# Control_Board_v1_1.net
KiCad netlist of a schematic drawn in EAGLE
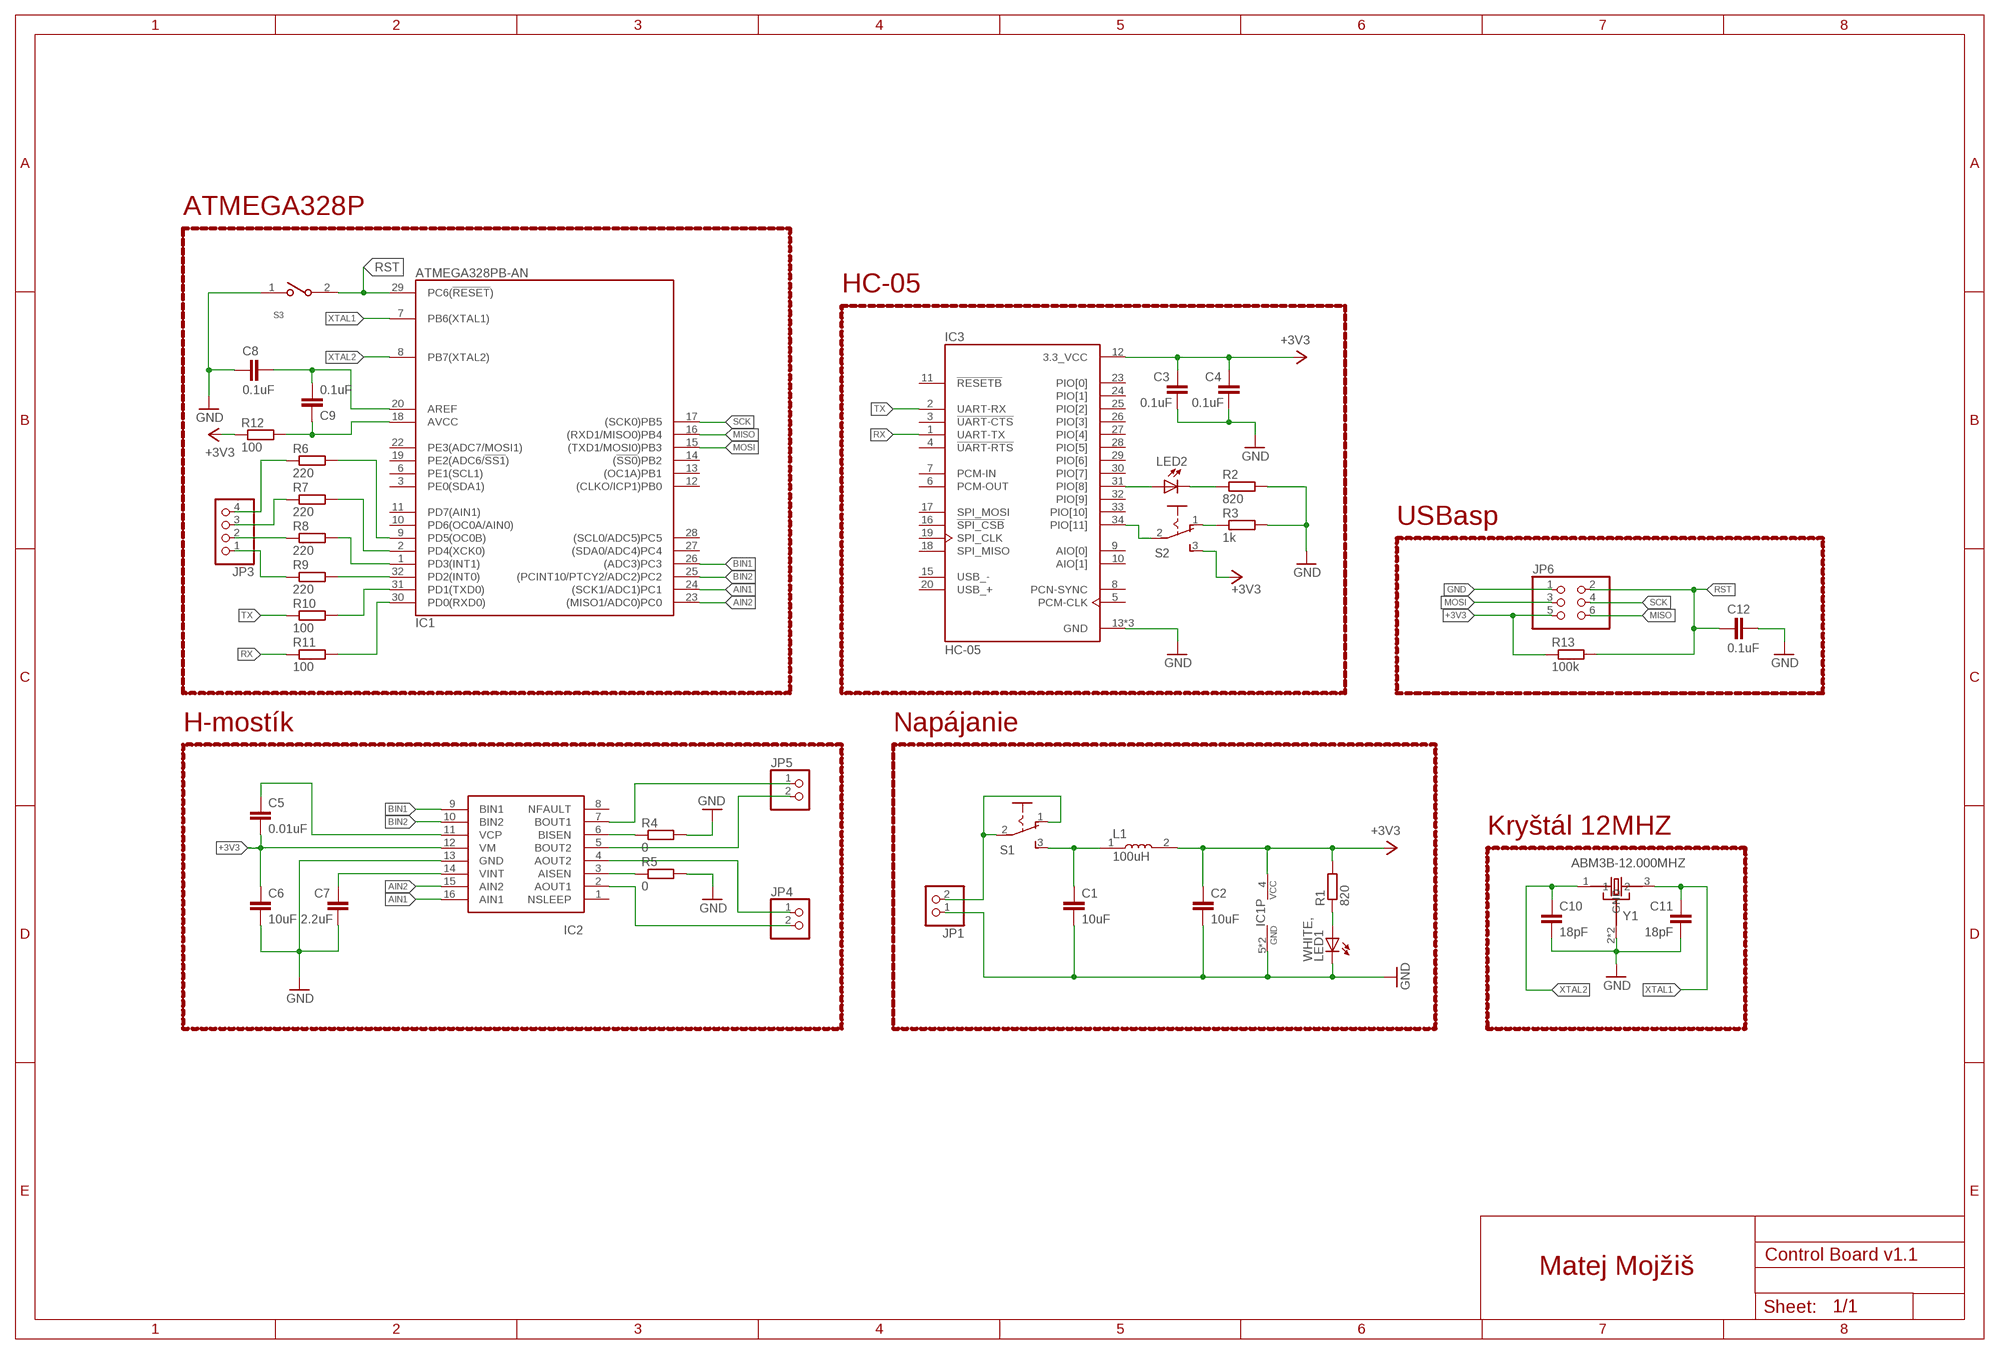
[diagram p0: schematic, sheet 1]

(export (version "E")
  (design (tool "Eeschema 10.0.6"))
  (components
    (comp (ref "C1")
      (value "10uF")
      (footprint "eagle-import:C0805")
      (libsource (lib "eagle-import") (part "C-EUC0805"))
    )
    (comp (ref "C2")
      (value "10uF")
      (footprint "eagle-import:C0805")
      (libsource (lib "eagle-import") (part "C-EUC0805"))
    )
    (comp (ref "C3")
      (value "0.1uF")
      (footprint "eagle-import:C0805")
      (libsource (lib "eagle-import") (part "C-EUC0805"))
    )
    (comp (ref "C4")
      (value "0.1uF")
      (footprint "eagle-import:C0805")
      (libsource (lib "eagle-import") (part "C-EUC0805"))
    )
    (comp (ref "C5")
      (value "0.01uF")
      (footprint "eagle-import:C0805")
      (libsource (lib "eagle-import") (part "C-EUC0805"))
    )
    (comp (ref "C6")
      (value "10uF")
      (footprint "eagle-import:C0805")
      (libsource (lib "eagle-import") (part "C-EUC0805"))
    )
    (comp (ref "C7")
      (value "2.2uF")
      (footprint "eagle-import:C0805")
      (libsource (lib "eagle-import") (part "C-EUC0805"))
    )
    (comp (ref "C8")
      (value "0.1uF")
      (footprint "eagle-import:C0805")
      (libsource (lib "eagle-import") (part "C-EUC0805"))
    )
    (comp (ref "C9")
      (value "0.1uF")
      (footprint "eagle-import:C0805")
      (libsource (lib "eagle-import") (part "C-EUC0805"))
    )
    (comp (ref "C10")
      (value "18pF")
      (footprint "eagle-import:C0805")
      (libsource (lib "eagle-import") (part "C-EUC0805"))
    )
    (comp (ref "C11")
      (value "18pF")
      (footprint "eagle-import:C0805")
      (libsource (lib "eagle-import") (part "C-EUC0805"))
    )
    (comp (ref "C12")
      (value "0.1uF")
      (footprint "eagle-import:C0805")
      (libsource (lib "eagle-import") (part "C-EUC0805"))
    )
    (comp (ref "IC1")
      (value "ATMEGA328PB-AN")
      (footprint "eagle-import:QFP32_7X7_0.80")
      (libsource (lib "eagle-import") (part "ATMEGA328PB-AN"))
    )
    (comp (ref "IC2")
      (value "DVR8833SUPERFICIAL")
      (footprint "eagle-import:PWP16")
      (libsource (lib "eagle-import") (part "DVR8833SUPERFICIAL"))
    )
    (comp (ref "IC3")
      (value "HC-05")
      (footprint "eagle-import:XCVR_HC-05")
      (fields (field (name "MF") "Bel Power solution"))
      (libsource (lib "eagle-import") (part "HC-05"))
    )
    (comp (ref "JP1")
      (value "PINHD-1X2/90")
      (footprint "eagle-import:1X02_90")
      (libsource (lib "eagle-import") (part "PINHD-1X2/90"))
    )
    (comp (ref "JP3")
      (value "PINHD-1X4")
      (footprint "eagle-import:1X04")
      (libsource (lib "eagle-import") (part "PINHD-1X4"))
    )
    (comp (ref "JP4")
      (value "PINHD-1X2/90")
      (footprint "eagle-import:1X02_90")
      (libsource (lib "eagle-import") (part "PINHD-1X2/90"))
    )
    (comp (ref "JP5")
      (value "PINHD-1X2/90")
      (footprint "eagle-import:1X02_90")
      (libsource (lib "eagle-import") (part "PINHD-1X2/90"))
    )
    (comp (ref "JP6")
      (value "PINHD-2X3")
      (footprint "eagle-import:2X03")
      (libsource (lib "eagle-import") (part "PINHD-2X3"))
    )
    (comp (ref "L1")
      (value "100uH")
      (footprint "eagle-import:INDC2012X87N")
      (fields (field (name "MF") "TDK") (field (name "MP") "MLF2012C330KT000"))
      (libsource (lib "eagle-import") (part "MLF2012C330KT000"))
    )
    (comp (ref "LED1")
      (value "WHITE,")
      (footprint "eagle-import:CHIPLED_0805")
      (libsource (lib "eagle-import") (part "LEDCHIPLED_0805"))
    )
    (comp (ref "LED2")
      (value "RED")
      (footprint "eagle-import:CHIPLED_0805")
      (libsource (lib "eagle-import") (part "LEDCHIPLED_0805"))
    )
    (comp (ref "R1")
      (value "820")
      (footprint "eagle-import:R0805")
      (libsource (lib "eagle-import") (part "R-EU_R0805"))
    )
    (comp (ref "R2")
      (value "820")
      (footprint "eagle-import:R0805")
      (libsource (lib "eagle-import") (part "R-EU_R0805"))
    )
    (comp (ref "R3")
      (value "1k")
      (footprint "eagle-import:R0805")
      (libsource (lib "eagle-import") (part "R-EU_R0805"))
    )
    (comp (ref "R4")
      (value "0")
      (footprint "eagle-import:R0805")
      (libsource (lib "eagle-import") (part "R-EU_R0805"))
    )
    (comp (ref "R5")
      (value "0")
      (footprint "eagle-import:R0805")
      (libsource (lib "eagle-import") (part "R-EU_R0805"))
    )
    (comp (ref "R6")
      (value "220")
      (footprint "eagle-import:R0805")
      (libsource (lib "eagle-import") (part "R-EU_R0805"))
    )
    (comp (ref "R7")
      (value "220")
      (footprint "eagle-import:R0805")
      (libsource (lib "eagle-import") (part "R-EU_R0805"))
    )
    (comp (ref "R8")
      (value "220")
      (footprint "eagle-import:R0805")
      (libsource (lib "eagle-import") (part "R-EU_R0805"))
    )
    (comp (ref "R9")
      (value "220")
      (footprint "eagle-import:R0805")
      (libsource (lib "eagle-import") (part "R-EU_R0805"))
    )
    (comp (ref "R10")
      (value "100")
      (footprint "eagle-import:R0805")
      (libsource (lib "eagle-import") (part "R-EU_R0805"))
    )
    (comp (ref "R11")
      (value "100")
      (footprint "eagle-import:R0805")
      (libsource (lib "eagle-import") (part "R-EU_R0805"))
    )
    (comp (ref "R12")
      (value "100")
      (footprint "eagle-import:R0805")
      (libsource (lib "eagle-import") (part "R-EU_R0805"))
    )
    (comp (ref "R13")
      (value "100k")
      (footprint "eagle-import:R0805")
      (libsource (lib "eagle-import") (part "R-EU_R0805"))
    )
    (comp (ref "S1")
      (value "255SB")
      (footprint "eagle-import:255SB")
      (libsource (lib "eagle-import") (part "255SB"))
    )
    (comp (ref "S2")
      (value "255SB")
      (footprint "eagle-import:255SB")
      (libsource (lib "eagle-import") (part "255SB"))
    )
    (comp (ref "S3")
      (value "147873-2")
      (footprint "eagle-import:SW_147873-2")
      (fields (field (name "MF") "TE Connectivity"))
      (libsource (lib "eagle-import") (part "147873-2"))
    )
    (comp (ref "Y1")
      (value "ABM3B-12.000MHZ")
      (footprint "eagle-import:OSCSC500X320X110-4N")
      (fields (field (name "MF") "Abracon") (field (name "MP") "ABM3B-8.000MHZ-B2-T"))
      (libsource (lib "eagle-import") (part "ABM3B-8.000MHZ-B2-T"))
    )
  )
  (nets
    (net (code "1") (name "+3V3") (class "Default")
      (node (ref "C2") (pin "1") (pinfunction "1_1") (pintype "passive"))
      (node (ref "C3") (pin "1") (pinfunction "1_1") (pintype "passive"))
      (node (ref "C4") (pin "1") (pinfunction "1_1") (pintype "passive"))
      (node (ref "C5") (pin "2") (pinfunction "2_2") (pintype "passive"))
      (node (ref "C6") (pin "1") (pinfunction "1_1") (pintype "passive"))
      (node (ref "IC1") (pin "4") (pinfunction "VCC_4") (pintype "power_in"))
      (node (ref "IC2") (pin "12") (pinfunction "VM_12") (pintype "bidirectional"))
      (node (ref "IC3") (pin "12") (pinfunction "3.3_VCC_12") (pintype "power_in"))
      (node (ref "JP6") (pin "5") (pinfunction "5_5") (pintype "passive"))
      (node (ref "L1") (pin "2") (pinfunction "2_2") (pintype "passive"))
      (node (ref "R1") (pin "2") (pinfunction "2_2") (pintype "passive"))
      (node (ref "R12") (pin "1") (pinfunction "1_1") (pintype "passive"))
      (node (ref "R13") (pin "1") (pinfunction "1_1") (pintype "passive"))
      (node (ref "S2") (pin "3") (pinfunction "S_3") (pintype "passive"))
    )
    (net (code "2") (name "AIN1") (class "Default")
      (node (ref "IC1") (pin "24") (pinfunction "(SCK1/ADC1)PC1_24") (pintype "bidirectional"))
      (node (ref "IC2") (pin "16") (pinfunction "AIN1_16") (pintype "bidirectional"))
    )
    (net (code "3") (name "AIN2") (class "Default")
      (node (ref "IC1") (pin "23") (pinfunction "(MISO1/ADC0)PC0_23") (pintype "bidirectional"))
      (node (ref "IC2") (pin "15") (pinfunction "AIN2_15") (pintype "bidirectional"))
    )
    (net (code "4") (name "BIN1") (class "Default")
      (node (ref "IC1") (pin "26") (pinfunction "(ADC3)PC3_26") (pintype "bidirectional"))
      (node (ref "IC2") (pin "9") (pinfunction "BIN1_9") (pintype "bidirectional"))
    )
    (net (code "5") (name "BIN2") (class "Default")
      (node (ref "IC1") (pin "25") (pinfunction "(PCINT10/PTCY2/ADC2)PC2_25") (pintype "bidirectional"))
      (node (ref "IC2") (pin "10") (pinfunction "BIN2_10") (pintype "bidirectional"))
    )
    (net (code "6") (name "GND") (class "Default")
      (node (ref "C1") (pin "2") (pinfunction "2_2") (pintype "passive"))
      (node (ref "C10") (pin "2") (pinfunction "2_2") (pintype "passive"))
      (node (ref "C11") (pin "2") (pinfunction "2_2") (pintype "passive"))
      (node (ref "C12") (pin "1") (pinfunction "1_1") (pintype "passive"))
      (node (ref "C2") (pin "2") (pinfunction "2_2") (pintype "passive"))
      (node (ref "C3") (pin "2") (pinfunction "2_2") (pintype "passive"))
      (node (ref "C4") (pin "2") (pinfunction "2_2") (pintype "passive"))
      (node (ref "C6") (pin "2") (pinfunction "2_2") (pintype "passive"))
      (node (ref "C7") (pin "2") (pinfunction "2_2") (pintype "passive"))
      (node (ref "C8") (pin "2") (pinfunction "2_2") (pintype "passive"))
      (node (ref "IC1") (pin "21") (pinfunction "GND_21") (pintype "power_in"))
      (node (ref "IC1") (pin "5") (pinfunction "GND_5") (pintype "power_in"))
      (node (ref "IC2") (pin "13") (pinfunction "GND_13") (pintype "bidirectional"))
      (node (ref "IC3") (pin "13") (pinfunction "GND_13") (pintype "power_in"))
      (node (ref "IC3") (pin "21") (pinfunction "GND_21") (pintype "power_in"))
      (node (ref "IC3") (pin "22") (pinfunction "GND_22") (pintype "power_in"))
      (node (ref "JP1") (pin "1") (pinfunction "1_1") (pintype "passive"))
      (node (ref "JP6") (pin "1") (pinfunction "1_1") (pintype "passive"))
      (node (ref "LED1") (pin "C") (pinfunction "C_C") (pintype "passive"))
      (node (ref "R2") (pin "2") (pinfunction "2_2") (pintype "passive"))
      (node (ref "R3") (pin "2") (pinfunction "2_2") (pintype "passive"))
      (node (ref "R4") (pin "2") (pinfunction "2_2") (pintype "passive"))
      (node (ref "R5") (pin "2") (pinfunction "2_2") (pintype "passive"))
      (node (ref "S3") (pin "1") (pinfunction "1_1") (pintype "passive"))
      (node (ref "Y1") (pin "2") (pinfunction "GND_2") (pintype "passive"))
      (node (ref "Y1") (pin "4") (pinfunction "GND_4") (pintype "passive"))
    )
    (net (code "7") (name "MISO") (class "Default")
      (node (ref "IC1") (pin "16") (pinfunction "(RXD1/MISO0)PB4_16") (pintype "bidirectional"))
      (node (ref "JP6") (pin "6") (pinfunction "6_6") (pintype "passive"))
    )
    (net (code "8") (name "MOSI") (class "Default")
      (node (ref "IC1") (pin "15") (pinfunction "(TXD1/MOSI0)PB3_15") (pintype "bidirectional"))
      (node (ref "JP6") (pin "3") (pinfunction "3_3") (pintype "passive"))
    )
    (net (code "9") (name "Net-(IC1A-AREF)") (class "Default")
      (node (ref "C8") (pin "1") (pinfunction "1_1") (pintype "passive"))
      (node (ref "C9") (pin "2") (pinfunction "2_2") (pintype "passive"))
      (node (ref "IC1") (pin "20") (pinfunction "AREF_20") (pintype "passive"))
    )
    (net (code "10") (name "Net-(IC1A-AVCC)") (class "Default")
      (node (ref "C9") (pin "1") (pinfunction "1_1") (pintype "passive"))
      (node (ref "IC1") (pin "18") (pinfunction "AVCC_18") (pintype "power_in"))
      (node (ref "R12") (pin "2") (pinfunction "2_2") (pintype "passive"))
    )
    (net (code "11") (name "Net-(IC1A-PD0(RXD0))") (class "Default")
      (node (ref "IC1") (pin "30") (pinfunction "PD0(RXD0)_30") (pintype "bidirectional"))
      (node (ref "R11") (pin "2") (pinfunction "2_2") (pintype "passive"))
    )
    (net (code "12") (name "Net-(IC1A-PD1(TXD0))") (class "Default")
      (node (ref "IC1") (pin "31") (pinfunction "PD1(TXD0)_31") (pintype "bidirectional"))
      (node (ref "R10") (pin "2") (pinfunction "2_2") (pintype "passive"))
    )
    (net (code "13") (name "Net-(IC1A-PD2(INT0))") (class "Default")
      (node (ref "IC1") (pin "32") (pinfunction "PD2(INT0)_32") (pintype "bidirectional"))
      (node (ref "R9") (pin "2") (pinfunction "2_2") (pintype "passive"))
    )
    (net (code "14") (name "Net-(IC1A-PD3(INT1))") (class "Default")
      (node (ref "IC1") (pin "1") (pinfunction "PD3(INT1)_1") (pintype "bidirectional"))
      (node (ref "R8") (pin "2") (pinfunction "2_2") (pintype "passive"))
    )
    (net (code "15") (name "Net-(IC1A-PD4(XCK0))") (class "Default")
      (node (ref "IC1") (pin "2") (pinfunction "PD4(XCK0)_2") (pintype "bidirectional"))
      (node (ref "R7") (pin "2") (pinfunction "2_2") (pintype "passive"))
    )
    (net (code "16") (name "Net-(IC1A-PD5(OC0B))") (class "Default")
      (node (ref "IC1") (pin "9") (pinfunction "PD5(OC0B)_9") (pintype "bidirectional"))
      (node (ref "R6") (pin "2") (pinfunction "2_2") (pintype "passive"))
    )
    (net (code "17") (name "Net-(IC2-AISEN)") (class "Default")
      (node (ref "IC2") (pin "3") (pinfunction "AISEN_3") (pintype "bidirectional"))
      (node (ref "R5") (pin "1") (pinfunction "1_1") (pintype "passive"))
    )
    (net (code "18") (name "Net-(IC2-AOUT1)") (class "Default")
      (node (ref "IC2") (pin "2") (pinfunction "AOUT1_2") (pintype "bidirectional"))
      (node (ref "JP4") (pin "2") (pinfunction "2_2") (pintype "passive"))
    )
    (net (code "19") (name "Net-(IC2-AOUT2)") (class "Default")
      (node (ref "IC2") (pin "4") (pinfunction "AOUT2_4") (pintype "bidirectional"))
      (node (ref "JP4") (pin "1") (pinfunction "1_1") (pintype "passive"))
    )
    (net (code "20") (name "Net-(IC2-BISEN)") (class "Default")
      (node (ref "IC2") (pin "6") (pinfunction "BISEN_6") (pintype "bidirectional"))
      (node (ref "R4") (pin "1") (pinfunction "1_1") (pintype "passive"))
    )
    (net (code "21") (name "Net-(IC2-BOUT1)") (class "Default")
      (node (ref "IC2") (pin "7") (pinfunction "BOUT1_7") (pintype "bidirectional"))
      (node (ref "JP5") (pin "1") (pinfunction "1_1") (pintype "passive"))
    )
    (net (code "22") (name "Net-(IC2-BOUT2)") (class "Default")
      (node (ref "IC2") (pin "5") (pinfunction "BOUT2_5") (pintype "bidirectional"))
      (node (ref "JP5") (pin "2") (pinfunction "2_2") (pintype "passive"))
    )
    (net (code "23") (name "Net-(IC2-VCP)") (class "Default")
      (node (ref "C5") (pin "1") (pinfunction "1_1") (pintype "passive"))
      (node (ref "IC2") (pin "11") (pinfunction "VCP_11") (pintype "bidirectional"))
    )
    (net (code "24") (name "Net-(IC2-VINT)") (class "Default")
      (node (ref "C7") (pin "1") (pinfunction "1_1") (pintype "passive"))
      (node (ref "IC2") (pin "14") (pinfunction "VINT_14") (pintype "bidirectional"))
    )
    (net (code "25") (name "Net-(IC3-PIO[8])") (class "Default")
      (node (ref "IC3") (pin "31") (pinfunction "PIO[8]_31") (pintype "bidirectional"))
      (node (ref "LED2") (pin "A") (pinfunction "A_A") (pintype "passive"))
    )
    (net (code "26") (name "Net-(IC3-PIO[11])") (class "Default")
      (node (ref "IC3") (pin "34") (pinfunction "PIO[11]_34") (pintype "bidirectional"))
      (node (ref "S2") (pin "2") (pinfunction "P_2") (pintype "passive"))
    )
    (net (code "27") (name "Net-(JP3-Pad1)") (class "Default")
      (node (ref "JP3") (pin "1") (pinfunction "1_1") (pintype "passive"))
      (node (ref "R9") (pin "1") (pinfunction "1_1") (pintype "passive"))
    )
    (net (code "28") (name "Net-(JP3-Pad2)") (class "Default")
      (node (ref "JP3") (pin "2") (pinfunction "2_2") (pintype "passive"))
      (node (ref "R8") (pin "1") (pinfunction "1_1") (pintype "passive"))
    )
    (net (code "29") (name "Net-(JP3-Pad3)") (class "Default")
      (node (ref "JP3") (pin "3") (pinfunction "3_3") (pintype "passive"))
      (node (ref "R7") (pin "1") (pinfunction "1_1") (pintype "passive"))
    )
    (net (code "30") (name "Net-(JP3-Pad4)") (class "Default")
      (node (ref "JP3") (pin "4") (pinfunction "4_4") (pintype "passive"))
      (node (ref "R6") (pin "1") (pinfunction "1_1") (pintype "passive"))
    )
    (net (code "31") (name "Net-(LED1-PadA)") (class "Default")
      (node (ref "LED1") (pin "A") (pinfunction "A_A") (pintype "passive"))
      (node (ref "R1") (pin "1") (pinfunction "1_1") (pintype "passive"))
    )
    (net (code "32") (name "Net-(LED2-PadC)") (class "Default")
      (node (ref "LED2") (pin "C") (pinfunction "C_C") (pintype "passive"))
      (node (ref "R2") (pin "1") (pinfunction "1_1") (pintype "passive"))
    )
    (net (code "33") (name "Net-(S1-O)") (class "Default")
      (node (ref "JP1") (pin "2") (pinfunction "2_2") (pintype "passive"))
      (node (ref "S1") (pin "1") (pinfunction "O_1") (pintype "passive"))
      (node (ref "S1") (pin "2") (pinfunction "P_2") (pintype "passive"))
    )
    (net (code "34") (name "Net-(S1-S)") (class "Default")
      (node (ref "C1") (pin "1") (pinfunction "1_1") (pintype "passive"))
      (node (ref "L1") (pin "1") (pinfunction "1_1") (pintype "passive"))
      (node (ref "S1") (pin "3") (pinfunction "S_3") (pintype "passive"))
    )
    (net (code "35") (name "Net-(S2-O)") (class "Default")
      (node (ref "R3") (pin "1") (pinfunction "1_1") (pintype "passive"))
      (node (ref "S2") (pin "1") (pinfunction "O_1") (pintype "passive"))
    )
    (net (code "36") (name "RST") (class "Default")
      (node (ref "C12") (pin "2") (pinfunction "2_2") (pintype "passive"))
      (node (ref "IC1") (pin "29") (pinfunction "PC6(~{RESET})_29") (pintype "bidirectional"))
      (node (ref "JP6") (pin "2") (pinfunction "2_2") (pintype "passive"))
      (node (ref "R13") (pin "2") (pinfunction "2_2") (pintype "passive"))
      (node (ref "S3") (pin "2") (pinfunction "2_2") (pintype "passive"))
    )
    (net (code "37") (name "RX") (class "Default")
      (node (ref "IC3") (pin "1") (pinfunction "UART-TX_1") (pintype "output"))
      (node (ref "R11") (pin "1") (pinfunction "1_1") (pintype "passive"))
    )
    (net (code "38") (name "SCK") (class "Default")
      (node (ref "IC1") (pin "17") (pinfunction "(SCK0)PB5_17") (pintype "bidirectional"))
      (node (ref "JP6") (pin "4") (pinfunction "4_4") (pintype "passive"))
    )
    (net (code "39") (name "TX") (class "Default")
      (node (ref "IC3") (pin "2") (pinfunction "UART-RX_2") (pintype "input"))
      (node (ref "R10") (pin "1") (pinfunction "1_1") (pintype "passive"))
    )
    (net (code "40") (name "XTAL1") (class "Default")
      (node (ref "C11") (pin "1") (pinfunction "1_1") (pintype "passive"))
      (node (ref "IC1") (pin "7") (pinfunction "PB6(XTAL1)_7") (pintype "bidirectional"))
      (node (ref "Y1") (pin "3") (pinfunction "2_3") (pintype "passive"))
    )
    (net (code "41") (name "XTAL2") (class "Default")
      (node (ref "C10") (pin "1") (pinfunction "1_1") (pintype "passive"))
      (node (ref "IC1") (pin "8") (pinfunction "PB7(XTAL2)_8") (pintype "bidirectional"))
      (node (ref "Y1") (pin "1") (pinfunction "1_1") (pintype "passive"))
    )
    (net (code "42") (name "unconnected-(IC1A-(CLKO{slash}ICP1)PB0-Pad12)") (class "Default")
      (node (ref "IC1") (pin "12") (pinfunction "(CLKO/ICP1)PB0_12") (pintype "bidirectional"))
    )
    (net (code "43") (name "unconnected-(IC1A-(OC1A)PB1-Pad13)") (class "Default")
      (node (ref "IC1") (pin "13") (pinfunction "(OC1A)PB1_13") (pintype "bidirectional"))
    )
    (net (code "44") (name "unconnected-(IC1A-(SCL0{slash}ADC5)PC5-Pad28)") (class "Default")
      (node (ref "IC1") (pin "28") (pinfunction "(SCL0/ADC5)PC5_28") (pintype "bidirectional"))
    )
    (net (code "45") (name "unconnected-(IC1A-(SDA0{slash}ADC4)PC4-Pad27)") (class "Default")
      (node (ref "IC1") (pin "27") (pinfunction "(SDA0/ADC4)PC4_27") (pintype "bidirectional"))
    )
    (net (code "46") (name "unconnected-(IC1A-(~{SS0})PB2-Pad14)") (class "Default")
      (node (ref "IC1") (pin "14") (pinfunction "(~{SS0})PB2_14") (pintype "bidirectional"))
    )
    (net (code "47") (name "unconnected-(IC1A-PD6(OC0A{slash}AIN0)-Pad10)") (class "Default")
      (node (ref "IC1") (pin "10") (pinfunction "PD6(OC0A/AIN0)_10") (pintype "bidirectional"))
    )
    (net (code "48") (name "unconnected-(IC1A-PD7(AIN1)-Pad11)") (class "Default")
      (node (ref "IC1") (pin "11") (pinfunction "PD7(AIN1)_11") (pintype "bidirectional"))
    )
    (net (code "49") (name "unconnected-(IC1A-PE0(SDA1)-Pad3)") (class "Default")
      (node (ref "IC1") (pin "3") (pinfunction "PE0(SDA1)_3") (pintype "bidirectional"))
    )
    (net (code "50") (name "unconnected-(IC1A-PE1(SCL1)-Pad6)") (class "Default")
      (node (ref "IC1") (pin "6") (pinfunction "PE1(SCL1)_6") (pintype "bidirectional"))
    )
    (net (code "51") (name "unconnected-(IC1A-PE2(ADC6{slash}~{SS1})-Pad19)") (class "Default")
      (node (ref "IC1") (pin "19") (pinfunction "PE2(ADC6/~{SS1})_19") (pintype "bidirectional"))
    )
    (net (code "52") (name "unconnected-(IC1A-PE3(ADC7{slash}MOSI1)-Pad22)") (class "Default")
      (node (ref "IC1") (pin "22") (pinfunction "PE3(ADC7/MOSI1)_22") (pintype "bidirectional"))
    )
    (net (code "53") (name "unconnected-(IC2-NFAULT-Pad8)") (class "Default")
      (node (ref "IC2") (pin "8") (pinfunction "NFAULT_8") (pintype "bidirectional"))
    )
    (net (code "54") (name "unconnected-(IC2-NSLEEP-Pad1)") (class "Default")
      (node (ref "IC2") (pin "1") (pinfunction "NSLEEP_1") (pintype "bidirectional"))
    )
    (net (code "55") (name "unconnected-(IC3-AIO[0]-Pad9)") (class "Default")
      (node (ref "IC3") (pin "9") (pinfunction "AIO[0]_9") (pintype "bidirectional"))
    )
    (net (code "56") (name "unconnected-(IC3-AIO[1]-Pad10)") (class "Default")
      (node (ref "IC3") (pin "10") (pinfunction "AIO[1]_10") (pintype "bidirectional"))
    )
    (net (code "57") (name "unconnected-(IC3-PCM-CLK-Pad5)") (class "Default")
      (node (ref "IC3") (pin "5") (pinfunction "PCM-CLK_5") (pintype "bidirectional"))
    )
    (net (code "58") (name "unconnected-(IC3-PCM-IN-Pad7)") (class "Default")
      (node (ref "IC3") (pin "7") (pinfunction "PCM-IN_7") (pintype "input"))
    )
    (net (code "59") (name "unconnected-(IC3-PCM-OUT-Pad6)") (class "Default")
      (node (ref "IC3") (pin "6") (pinfunction "PCM-OUT_6") (pintype "output"))
    )
    (net (code "60") (name "unconnected-(IC3-PCN-SYNC-Pad8)") (class "Default")
      (node (ref "IC3") (pin "8") (pinfunction "PCN-SYNC_8") (pintype "bidirectional"))
    )
    (net (code "61") (name "unconnected-(IC3-PIO[0]-Pad23)") (class "Default")
      (node (ref "IC3") (pin "23") (pinfunction "PIO[0]_23") (pintype "bidirectional"))
    )
    (net (code "62") (name "unconnected-(IC3-PIO[1]-Pad24)") (class "Default")
      (node (ref "IC3") (pin "24") (pinfunction "PIO[1]_24") (pintype "bidirectional"))
    )
    (net (code "63") (name "unconnected-(IC3-PIO[2]-Pad25)") (class "Default")
      (node (ref "IC3") (pin "25") (pinfunction "PIO[2]_25") (pintype "bidirectional"))
    )
    (net (code "64") (name "unconnected-(IC3-PIO[3]-Pad26)") (class "Default")
      (node (ref "IC3") (pin "26") (pinfunction "PIO[3]_26") (pintype "bidirectional"))
    )
    (net (code "65") (name "unconnected-(IC3-PIO[4]-Pad27)") (class "Default")
      (node (ref "IC3") (pin "27") (pinfunction "PIO[4]_27") (pintype "bidirectional"))
    )
    (net (code "66") (name "unconnected-(IC3-PIO[5]-Pad28)") (class "Default")
      (node (ref "IC3") (pin "28") (pinfunction "PIO[5]_28") (pintype "bidirectional"))
    )
    (net (code "67") (name "unconnected-(IC3-PIO[6]-Pad29)") (class "Default")
      (node (ref "IC3") (pin "29") (pinfunction "PIO[6]_29") (pintype "bidirectional"))
    )
    (net (code "68") (name "unconnected-(IC3-PIO[7]-Pad30)") (class "Default")
      (node (ref "IC3") (pin "30") (pinfunction "PIO[7]_30") (pintype "bidirectional"))
    )
    (net (code "69") (name "unconnected-(IC3-PIO[9]-Pad32)") (class "Default")
      (node (ref "IC3") (pin "32") (pinfunction "PIO[9]_32") (pintype "bidirectional"))
    )
    (net (code "70") (name "unconnected-(IC3-PIO[10]-Pad33)") (class "Default")
      (node (ref "IC3") (pin "33") (pinfunction "PIO[10]_33") (pintype "bidirectional"))
    )
    (net (code "71") (name "unconnected-(IC3-SPI_CLK-Pad19)") (class "Default")
      (node (ref "IC3") (pin "19") (pinfunction "SPI_CLK_19") (pintype "input"))
    )
    (net (code "72") (name "unconnected-(IC3-SPI_MISO-Pad18)") (class "Default")
      (node (ref "IC3") (pin "18") (pinfunction "SPI_MISO_18") (pintype "output"))
    )
    (net (code "73") (name "unconnected-(IC3-SPI_MOSI-Pad17)") (class "Default")
      (node (ref "IC3") (pin "17") (pinfunction "SPI_MOSI_17") (pintype "input"))
    )
    (net (code "74") (name "unconnected-(IC3-USB_+-Pad20)") (class "Default")
      (node (ref "IC3") (pin "20") (pinfunction "USB_+_20") (pintype "bidirectional"))
    )
    (net (code "75") (name "unconnected-(IC3-USB_--Pad15)") (class "Default")
      (node (ref "IC3") (pin "15") (pinfunction "USB_-_15") (pintype "bidirectional"))
    )
    (net (code "76") (name "unconnected-(IC3-~{RESETB}-Pad11)") (class "Default")
      (node (ref "IC3") (pin "11") (pinfunction "~{RESETB}_11") (pintype "input"))
    )
    (net (code "77") (name "unconnected-(IC3-~{SPI_CSB}-Pad16)") (class "Default")
      (node (ref "IC3") (pin "16") (pinfunction "~{SPI_CSB}_16") (pintype "input"))
    )
    (net (code "78") (name "unconnected-(IC3-~{UART-CTS}-Pad3)") (class "Default")
      (node (ref "IC3") (pin "3") (pinfunction "~{UART-CTS}_3") (pintype "input"))
    )
    (net (code "79") (name "unconnected-(IC3-~{UART-RTS}-Pad4)") (class "Default")
      (node (ref "IC3") (pin "4") (pinfunction "~{UART-RTS}_4") (pintype "output"))
    )
  )
)
